# Ethernet.net
KiCad netlist of a schematic drawn in Altium Designer
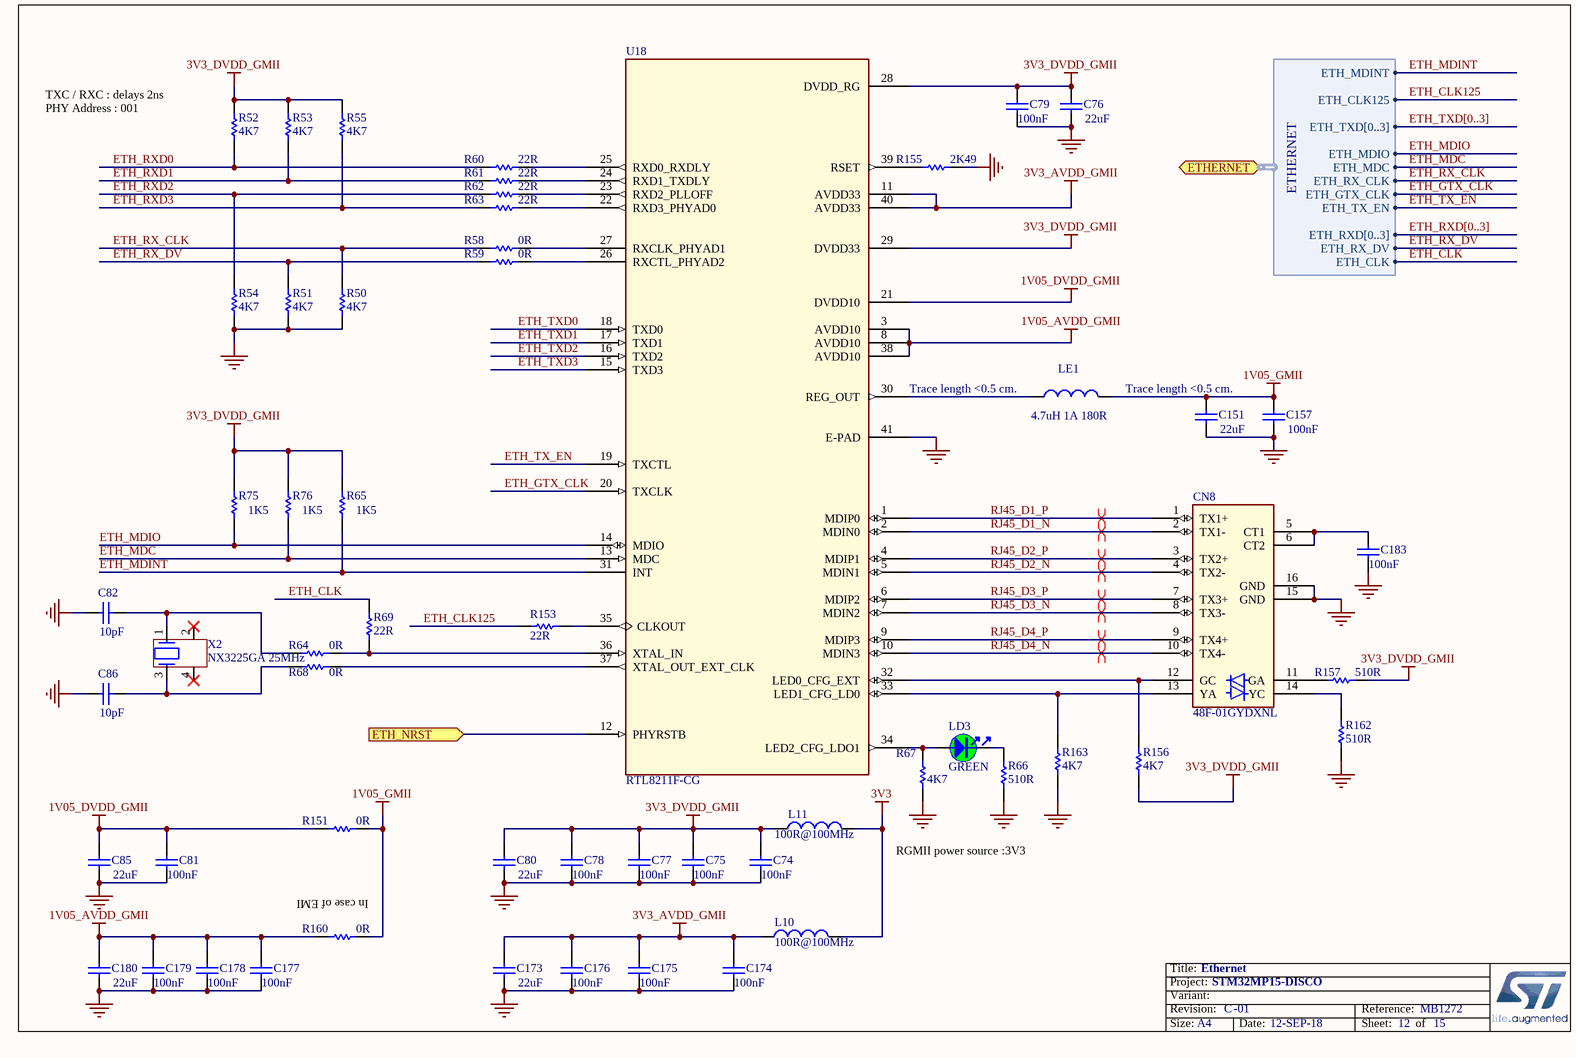
[diagram p0: Ethernet.SchDoc]

(export (version "E")
  (design (tool "Eeschema 10.0.6"))
  (components
    (comp (ref "C74")
      (value "100nF")
      (footprint "C0402")
      (description "Capacitor,100nF,16V,X7R,10%,0402")
      (fields
        (field (name "INTERNAL_PART_NUMBER") "MCD-00006")
        (field (name "MANUFACTURER_PART_NUMBER") "CC0402KRX7R7BB104")
        (field (name "PROVIDED_BY") "SUBCO")
      )
      (libsource (lib "MCD_PARTS_database") (part "Capacitor"))
    )
    (comp (ref "C75")
      (value "100nF")
      (footprint "C0402")
      (description "Capacitor,100nF,16V,X7R,10%,0402")
      (fields
        (field (name "INTERNAL_PART_NUMBER") "MCD-00006")
        (field (name "MANUFACTURER_PART_NUMBER") "CC0402KRX7R7BB104")
        (field (name "PROVIDED_BY") "SUBCO")
      )
      (libsource (lib "MCD_PARTS_database") (part "Capacitor"))
    )
    (comp (ref "C76")
      (value "22uF")
      (footprint "C0603")
      (description "Capacitor,22uF,6V3,X5R,20%,0603")
      (fields
        (field (name "INTERNAL_PART_NUMBER") "MCD-00100")
        (field (name "MANUFACTURER_PART_NUMBER") "GRM188R60J226MEA0J")
        (field (name "PROVIDED_BY") "SUBCO")
      )
      (libsource (lib "MCD_PARTS_database") (part "Capacitor"))
    )
    (comp (ref "C77")
      (value "100nF")
      (footprint "C0402")
      (description "Capacitor,100nF,16V,X7R,10%,0402")
      (fields
        (field (name "INTERNAL_PART_NUMBER") "MCD-00006")
        (field (name "MANUFACTURER_PART_NUMBER") "CC0402KRX7R7BB104")
        (field (name "PROVIDED_BY") "SUBCO")
      )
      (libsource (lib "MCD_PARTS_database") (part "Capacitor"))
    )
    (comp (ref "C78")
      (value "100nF")
      (footprint "C0402")
      (description "Capacitor,100nF,16V,X7R,10%,0402")
      (fields
        (field (name "INTERNAL_PART_NUMBER") "MCD-00006")
        (field (name "MANUFACTURER_PART_NUMBER") "CC0402KRX7R7BB104")
        (field (name "PROVIDED_BY") "SUBCO")
      )
      (libsource (lib "MCD_PARTS_database") (part "Capacitor"))
    )
    (comp (ref "C79")
      (value "100nF")
      (footprint "C0402")
      (description "Capacitor,100nF,16V,X7R,10%,0402")
      (fields
        (field (name "INTERNAL_PART_NUMBER") "MCD-00006")
        (field (name "MANUFACTURER_PART_NUMBER") "CC0402KRX7R7BB104")
        (field (name "PROVIDED_BY") "SUBCO")
      )
      (libsource (lib "MCD_PARTS_database") (part "Capacitor"))
    )
    (comp (ref "C80")
      (value "22uF")
      (footprint "C0603")
      (description "Capacitor,22uF,6V3,X5R,20%,0603")
      (fields
        (field (name "INTERNAL_PART_NUMBER") "MCD-00100")
        (field (name "MANUFACTURER_PART_NUMBER") "GRM188R60J226MEA0J")
        (field (name "PROVIDED_BY") "SUBCO")
      )
      (libsource (lib "MCD_PARTS_database") (part "Capacitor"))
    )
    (comp (ref "C81")
      (value "100nF")
      (footprint "C0402")
      (description "Capacitor,100nF,16V,X7R,10%,0402")
      (fields
        (field (name "INTERNAL_PART_NUMBER") "MCD-00006")
        (field (name "MANUFACTURER_PART_NUMBER") "CC0402KRX7R7BB104")
        (field (name "PROVIDED_BY") "SUBCO")
      )
      (libsource (lib "MCD_PARTS_database") (part "Capacitor"))
    )
    (comp (ref "C82")
      (value "10pF")
      (footprint "C0402")
      (description "Capacitor,10pF,50V,NPO,5%,0402")
      (fields
        (field (name "INTERNAL_PART_NUMBER") "MCD-00015")
        (field (name "MANUFACTURER_PART_NUMBER") "CC0402JRNPO9BN100")
        (field (name "PROVIDED_BY") "SUBCO")
      )
      (libsource (lib "MCD_PARTS_database") (part "Capacitor"))
    )
    (comp (ref "C85")
      (value "22uF")
      (footprint "C0603")
      (description "Capacitor,22uF,6V3,X5R,20%,0603")
      (fields
        (field (name "INTERNAL_PART_NUMBER") "MCD-00100")
        (field (name "MANUFACTURER_PART_NUMBER") "GRM188R60J226MEA0J")
        (field (name "PROVIDED_BY") "SUBCO")
      )
      (libsource (lib "MCD_PARTS_database") (part "Capacitor"))
    )
    (comp (ref "C86")
      (value "10pF")
      (footprint "C0402")
      (description "Capacitor,10pF,50V,NPO,5%,0402")
      (fields
        (field (name "INTERNAL_PART_NUMBER") "MCD-00015")
        (field (name "MANUFACTURER_PART_NUMBER") "CC0402JRNPO9BN100")
        (field (name "PROVIDED_BY") "SUBCO")
      )
      (libsource (lib "MCD_PARTS_database") (part "Capacitor"))
    )
    (comp (ref "C151")
      (value "22uF")
      (footprint "C0603")
      (description "Capacitor,22uF,6V3,X5R,20%,0603")
      (fields
        (field (name "INTERNAL_PART_NUMBER") "MCD-00100")
        (field (name "MANUFACTURER_PART_NUMBER") "GRM188R60J226MEA0J")
        (field (name "PROVIDED_BY") "SUBCO")
      )
      (libsource (lib "MCD_PARTS_database") (part "Capacitor"))
    )
    (comp (ref "C157")
      (value "100nF")
      (footprint "C0402")
      (description "Capacitor,100nF,16V,X7R,10%,0402")
      (fields
        (field (name "INTERNAL_PART_NUMBER") "MCD-00006")
        (field (name "MANUFACTURER_PART_NUMBER") "CC0402KRX7R7BB104")
        (field (name "PROVIDED_BY") "SUBCO")
      )
      (libsource (lib "MCD_PARTS_database") (part "Capacitor"))
    )
    (comp (ref "C173")
      (value "22uF")
      (footprint "C0603")
      (description "Capacitor,22uF,6V3,X5R,20%,0603")
      (fields
        (field (name "INTERNAL_PART_NUMBER") "MCD-00100")
        (field (name "MANUFACTURER_PART_NUMBER") "GRM188R60J226MEA0J")
        (field (name "PROVIDED_BY") "SUBCO")
      )
      (libsource (lib "MCD_PARTS_database") (part "Capacitor"))
    )
    (comp (ref "C174")
      (value "100nF")
      (footprint "C0402")
      (description "Capacitor,100nF,16V,X7R,10%,0402")
      (fields
        (field (name "INTERNAL_PART_NUMBER") "MCD-00006")
        (field (name "MANUFACTURER_PART_NUMBER") "CC0402KRX7R7BB104")
        (field (name "PROVIDED_BY") "SUBCO")
      )
      (libsource (lib "MCD_PARTS_database") (part "Capacitor"))
    )
    (comp (ref "C175")
      (value "100nF")
      (footprint "C0402")
      (description "Capacitor,100nF,16V,X7R,10%,0402")
      (fields
        (field (name "INTERNAL_PART_NUMBER") "MCD-00006")
        (field (name "MANUFACTURER_PART_NUMBER") "CC0402KRX7R7BB104")
        (field (name "PROVIDED_BY") "SUBCO")
      )
      (libsource (lib "MCD_PARTS_database") (part "Capacitor"))
    )
    (comp (ref "C176")
      (value "100nF")
      (footprint "C0402")
      (description "Capacitor,100nF,16V,X7R,10%,0402")
      (fields
        (field (name "INTERNAL_PART_NUMBER") "MCD-00006")
        (field (name "MANUFACTURER_PART_NUMBER") "CC0402KRX7R7BB104")
        (field (name "PROVIDED_BY") "SUBCO")
      )
      (libsource (lib "MCD_PARTS_database") (part "Capacitor"))
    )
    (comp (ref "C177")
      (value "100nF")
      (footprint "C0402")
      (description "Capacitor,100nF,16V,X7R,10%,0402")
      (fields
        (field (name "INTERNAL_PART_NUMBER") "MCD-00006")
        (field (name "MANUFACTURER_PART_NUMBER") "CC0402KRX7R7BB104")
        (field (name "PROVIDED_BY") "SUBCO")
      )
      (libsource (lib "MCD_PARTS_database") (part "Capacitor"))
    )
    (comp (ref "C178")
      (value "100nF")
      (footprint "C0402")
      (description "Capacitor,100nF,16V,X7R,10%,0402")
      (fields
        (field (name "INTERNAL_PART_NUMBER") "MCD-00006")
        (field (name "MANUFACTURER_PART_NUMBER") "CC0402KRX7R7BB104")
        (field (name "PROVIDED_BY") "SUBCO")
      )
      (libsource (lib "MCD_PARTS_database") (part "Capacitor"))
    )
    (comp (ref "C179")
      (value "100nF")
      (footprint "C0402")
      (description "Capacitor,100nF,16V,X7R,10%,0402")
      (fields
        (field (name "INTERNAL_PART_NUMBER") "MCD-00006")
        (field (name "MANUFACTURER_PART_NUMBER") "CC0402KRX7R7BB104")
        (field (name "PROVIDED_BY") "SUBCO")
      )
      (libsource (lib "MCD_PARTS_database") (part "Capacitor"))
    )
    (comp (ref "C180")
      (value "22uF")
      (footprint "C0603")
      (description "Capacitor,22uF,6V3,X5R,20%,0603")
      (fields
        (field (name "INTERNAL_PART_NUMBER") "MCD-00100")
        (field (name "MANUFACTURER_PART_NUMBER") "GRM188R60J226MEA0J")
        (field (name "PROVIDED_BY") "SUBCO")
      )
      (libsource (lib "MCD_PARTS_database") (part "Capacitor"))
    )
    (comp (ref "C183")
      (value "100nF")
      (footprint "C0402")
      (description "Capacitor,100nF,16V,X7R,10%,0402")
      (fields
        (field (name "INTERNAL_PART_NUMBER") "MCD-00006")
        (field (name "MANUFACTURER_PART_NUMBER") "CC0402KRX7R7BB104")
        (field (name "PROVIDED_BY") "SUBCO")
      )
      (libsource (lib "MCD_PARTS_database") (part "Capacitor"))
    )
    (comp (ref "CN8")
      (value "48F-01GYDXNL")
      (footprint "CON_RJ45_YD_48F-01GYDXNL_LED-P")
      (description "Connector RJ45 with Gigabit magnetics and LED , led pull down")
      (fields
        (field (name "INTERNAL_PART_NUMBER") "MCD-01129")
        (field (name "MANUFACTURER") "YUAN DEAN SCIENTIFIC")
        (field (name "PROVIDED_BY") "SUBCO")
      )
      (libsource (lib "MCD_PARTS_database") (part "RJ45_48F_01GYDXNL_LPD"))
    )
    (comp (ref "L10")
      (value "100R@100MHz")
      (footprint "FIL_0603_H0P65")
      (description "Ferrite bead 100R 2A 0603")
      (fields
        (field (name "INTERNAL_PART_NUMBER") "MCD-00094")
        (field (name "MANUFACTURER_PART_NUMBER") "BLM18EG101TN1")
        (field (name "PROVIDED_BY") "SUBCO")
      )
      (libsource (lib "MCD_PARTS_database") (part "BEAD"))
    )
    (comp (ref "L11")
      (value "100R@100MHz")
      (footprint "FIL_0603_H0P65")
      (description "Ferrite bead 100R 2A 0603")
      (fields
        (field (name "INTERNAL_PART_NUMBER") "MCD-00094")
        (field (name "MANUFACTURER_PART_NUMBER") "BLM18EG101TN1")
        (field (name "PROVIDED_BY") "SUBCO")
      )
      (libsource (lib "MCD_PARTS_database") (part "BEAD"))
    )
    (comp (ref "LD3")
      (value "GREEN")
      (footprint "LED_0603_GREEN")
      (description "LED, Green, 0603")
      (fields
        (field (name "INTERNAL_PART_NUMBER") "MCD-00050")
        (field (name "MANUFACTURER_PART_NUMBER") "19-213SYGC/S530-E2/TR8")
        (field (name "PROVIDED_BY") "SUBCO")
      )
      (libsource (lib "MCD_PARTS_database") (part "LED_green"))
    )
    (comp (ref "LE1")
      (value "4.7uH 1A 180R")
      (footprint "L1210_LQH")
      (description "FIXED IND 4.7UH 1A 180 MOHM 30% SMD")
      (fields
        (field (name "INTERNAL_PART_NUMBER") "MCD-00048")
        (field (name "MANUFACTURER_PART_NUMBER") "LQH32PN4R7NN0L")
        (field (name "PROVIDED_BY") "SUBCO")
      )
      (libsource (lib "MCD_PARTS_database") (part "Inductor"))
    )
    (comp (ref "R50")
      (value "4K7")
      (footprint "R0402")
      (description "Resistor,4K7,0402,1%,1/16W")
      (fields
        (field (name "INTERNAL_PART_NUMBER") "MCD-00065")
        (field (name "MANUFACTURER_PART_NUMBER") "RC0402FR-074K7L")
        (field (name "PROVIDED_BY") "SUBCO")
      )
      (libsource (lib "MCD_PARTS_database") (part "Resistor"))
    )
    (comp (ref "R51")
      (value "4K7")
      (footprint "R0402")
      (description "Resistor,4K7,0402,1%,1/16W")
      (fields
        (field (name "INTERNAL_PART_NUMBER") "MCD-00065")
        (field (name "MANUFACTURER_PART_NUMBER") "RC0402FR-074K7L")
        (field (name "PROVIDED_BY") "SUBCO")
      )
      (libsource (lib "MCD_PARTS_database") (part "Resistor"))
    )
    (comp (ref "R52")
      (value "4K7")
      (footprint "R0402")
      (description "Resistor,4K7,0402,1%,1/16W")
      (fields
        (field (name "INTERNAL_PART_NUMBER") "MCD-00065")
        (field (name "MANUFACTURER_PART_NUMBER") "RC0402FR-074K7L")
        (field (name "PROVIDED_BY") "SUBCO")
      )
      (libsource (lib "MCD_PARTS_database") (part "Resistor"))
    )
    (comp (ref "R53")
      (value "4K7")
      (footprint "R0402")
      (description "Resistor,4K7,0402,1%,1/16W")
      (fields
        (field (name "INTERNAL_PART_NUMBER") "MCD-00065")
        (field (name "MANUFACTURER_PART_NUMBER") "RC0402FR-074K7L")
        (field (name "PROVIDED_BY") "SUBCO")
      )
      (libsource (lib "MCD_PARTS_database") (part "Resistor"))
    )
    (comp (ref "R54")
      (value "4K7")
      (footprint "R0402")
      (description "Resistor,4K7,0402,1%,1/16W")
      (fields
        (field (name "INTERNAL_PART_NUMBER") "MCD-00065")
        (field (name "MANUFACTURER_PART_NUMBER") "RC0402FR-074K7L")
        (field (name "PROVIDED_BY") "SUBCO")
      )
      (libsource (lib "MCD_PARTS_database") (part "Resistor"))
    )
    (comp (ref "R55")
      (value "4K7")
      (footprint "R0402")
      (description "Resistor,4K7,0402,1%,1/16W")
      (fields
        (field (name "INTERNAL_PART_NUMBER") "MCD-00065")
        (field (name "MANUFACTURER_PART_NUMBER") "RC0402FR-074K7L")
        (field (name "PROVIDED_BY") "SUBCO")
      )
      (libsource (lib "MCD_PARTS_database") (part "Resistor"))
    )
    (comp (ref "R58")
      (value "0R")
      (footprint "R0402")
      (description "Resistor,0R,0402,5%,1/16W")
      (fields
        (field (name "INTERNAL_PART_NUMBER") "MCD-00052")
        (field (name "MANUFACTURER_PART_NUMBER") "RC0402JR-070RL")
        (field (name "PROVIDED_BY") "SUBCO")
      )
      (libsource (lib "MCD_PARTS_database") (part "Resistor"))
    )
    (comp (ref "R59")
      (value "0R")
      (footprint "R0402")
      (description "Resistor,0R,0402,5%,1/16W")
      (fields
        (field (name "INTERNAL_PART_NUMBER") "MCD-00052")
        (field (name "MANUFACTURER_PART_NUMBER") "RC0402JR-070RL")
        (field (name "PROVIDED_BY") "SUBCO")
      )
      (libsource (lib "MCD_PARTS_database") (part "Resistor"))
    )
    (comp (ref "R60")
      (value "22R")
      (footprint "R0402")
      (description "Resistor,22R,0402,1%,1/16W")
      (fields
        (field (name "INTERNAL_PART_NUMBER") "MCD-00189")
        (field (name "MANUFACTURER_PART_NUMBER") "RC0402FR-0722RL")
        (field (name "PROVIDED_BY") "SUBCO")
      )
      (libsource (lib "MCD_PARTS_database") (part "Resistor"))
    )
    (comp (ref "R61")
      (value "22R")
      (footprint "R0402")
      (description "Resistor,22R,0402,1%,1/16W")
      (fields
        (field (name "INTERNAL_PART_NUMBER") "MCD-00189")
        (field (name "MANUFACTURER_PART_NUMBER") "RC0402FR-0722RL")
        (field (name "PROVIDED_BY") "SUBCO")
      )
      (libsource (lib "MCD_PARTS_database") (part "Resistor"))
    )
    (comp (ref "R62")
      (value "22R")
      (footprint "R0402")
      (description "Resistor,22R,0402,1%,1/16W")
      (fields
        (field (name "INTERNAL_PART_NUMBER") "MCD-00189")
        (field (name "MANUFACTURER_PART_NUMBER") "RC0402FR-0722RL")
        (field (name "PROVIDED_BY") "SUBCO")
      )
      (libsource (lib "MCD_PARTS_database") (part "Resistor"))
    )
    (comp (ref "R63")
      (value "22R")
      (footprint "R0402")
      (description "Resistor,22R,0402,1%,1/16W")
      (fields
        (field (name "INTERNAL_PART_NUMBER") "MCD-00189")
        (field (name "MANUFACTURER_PART_NUMBER") "RC0402FR-0722RL")
        (field (name "PROVIDED_BY") "SUBCO")
      )
      (libsource (lib "MCD_PARTS_database") (part "Resistor"))
    )
    (comp (ref "R64")
      (value "0R")
      (footprint "R0402")
      (description "Resistor,0R,0402,5%,1/16W")
      (fields
        (field (name "INTERNAL_PART_NUMBER") "MCD-00052")
        (field (name "MANUFACTURER_PART_NUMBER") "RC0402JR-070RL")
        (field (name "PROVIDED_BY") "SUBCO")
      )
      (libsource (lib "MCD_PARTS_database") (part "Resistor"))
    )
    (comp (ref "R65")
      (value "1K5")
      (footprint "R0402")
      (description "Resistor,1K5,0402,1%,1/16W")
      (fields
        (field (name "INTERNAL_PART_NUMBER") "MCD-00068")
        (field (name "MANUFACTURER_PART_NUMBER") "RC0402FR-071K5L")
        (field (name "PROVIDED_BY") "SUBCO")
      )
      (libsource (lib "MCD_PARTS_database") (part "Resistor"))
    )
    (comp (ref "R66")
      (value "510R")
      (footprint "R0402")
      (description "Resistor,510R,0402,1%,1/16W")
      (fields
        (field (name "INTERNAL_PART_NUMBER") "MCD-00064")
        (field (name "MANUFACTURER_PART_NUMBER") "RC0402FR-07510RL")
        (field (name "PROVIDED_BY") "SUBCO")
      )
      (libsource (lib "MCD_PARTS_database") (part "Resistor"))
    )
    (comp (ref "R67")
      (value "4K7")
      (footprint "R0402")
      (description "Resistor,4K7,0402,1%,1/16W")
      (fields
        (field (name "INTERNAL_PART_NUMBER") "MCD-00065")
        (field (name "MANUFACTURER_PART_NUMBER") "RC0402FR-074K7L")
        (field (name "PROVIDED_BY") "SUBCO")
      )
      (libsource (lib "MCD_PARTS_database") (part "Resistor"))
    )
    (comp (ref "R68")
      (value "0R")
      (footprint "R0402")
      (description "Resistor,0R,0402,5%,1/16W")
      (fields
        (field (name "INTERNAL_PART_NUMBER") "MCD-00052")
        (field (name "MANUFACTURER_PART_NUMBER") "RC0402JR-070RL")
        (field (name "PROVIDED_BY") "SUBCO")
      )
      (libsource (lib "MCD_PARTS_database") (part "Resistor"))
    )
    (comp (ref "R69")
      (value "22R")
      (footprint "R0402")
      (description "Resistor,22R,0402,1%,1/16W")
      (fields
        (field (name "INTERNAL_PART_NUMBER") "MCD-00189")
        (field (name "MANUFACTURER_PART_NUMBER") "RC0402FR-0722RL")
        (field (name "PROVIDED_BY") "SUBCO")
      )
      (libsource (lib "MCD_PARTS_database") (part "Resistor"))
    )
    (comp (ref "R75")
      (value "1K5")
      (footprint "R0402")
      (description "Resistor,1K5,0402,1%,1/16W")
      (fields
        (field (name "INTERNAL_PART_NUMBER") "MCD-00068")
        (field (name "MANUFACTURER_PART_NUMBER") "RC0402FR-071K5L")
        (field (name "PROVIDED_BY") "SUBCO")
      )
      (libsource (lib "MCD_PARTS_database") (part "Resistor"))
    )
    (comp (ref "R76")
      (value "1K5")
      (footprint "R0402")
      (description "Resistor,1K5,0402,1%,1/16W")
      (fields
        (field (name "INTERNAL_PART_NUMBER") "MCD-00068")
        (field (name "MANUFACTURER_PART_NUMBER") "RC0402FR-071K5L")
        (field (name "PROVIDED_BY") "SUBCO")
      )
      (libsource (lib "MCD_PARTS_database") (part "Resistor"))
    )
    (comp (ref "R151")
      (value "0R")
      (footprint "R0603")
      (description "Resistor,0R,0603,5%,1/10W")
      (fields
        (field (name "INTERNAL_PART_NUMBER") "MCD-00056")
        (field (name "MANUFACTURER_PART_NUMBER") "RC0603JR-070RL")
        (field (name "PROVIDED_BY") "SUBCO")
      )
      (libsource (lib "MCD_PARTS_database") (part "Resistor"))
    )
    (comp (ref "R153")
      (value "22R")
      (footprint "R0402")
      (description "Resistor,22R,0402,1%,1/16W")
      (fields
        (field (name "INTERNAL_PART_NUMBER") "MCD-00189")
        (field (name "MANUFACTURER_PART_NUMBER") "RC0402FR-0722RL")
        (field (name "PROVIDED_BY") "SUBCO")
      )
      (libsource (lib "MCD_PARTS_database") (part "Resistor"))
    )
    (comp (ref "R155")
      (value "2K49")
      (footprint "R0402")
      (description "Resistor,2K49,0402,1%,1/16W")
      (fields
        (field (name "INTERNAL_PART_NUMBER") "MCD-00183")
        (field (name "MANUFACTURER_PART_NUMBER") "RC0402FR-072K49L")
        (field (name "PROVIDED_BY") "SUBCO")
      )
      (libsource (lib "MCD_PARTS_database") (part "Resistor"))
    )
    (comp (ref "R156")
      (value "4K7")
      (footprint "R0402")
      (description "Resistor,4K7,0402,1%,1/16W")
      (fields
        (field (name "INTERNAL_PART_NUMBER") "MCD-00065")
        (field (name "MANUFACTURER_PART_NUMBER") "RC0402FR-074K7L")
        (field (name "PROVIDED_BY") "SUBCO")
      )
      (libsource (lib "MCD_PARTS_database") (part "Resistor"))
    )
    (comp (ref "R157")
      (value "510R")
      (footprint "R0402")
      (description "Resistor,510R,0402,1%,1/16W")
      (fields
        (field (name "INTERNAL_PART_NUMBER") "MCD-00064")
        (field (name "MANUFACTURER_PART_NUMBER") "RC0402FR-07510RL")
        (field (name "PROVIDED_BY") "SUBCO")
      )
      (libsource (lib "MCD_PARTS_database") (part "Resistor"))
    )
    (comp (ref "R160")
      (value "0R")
      (footprint "R0603")
      (description "Resistor,0R,0603,5%,1/10W")
      (fields
        (field (name "INTERNAL_PART_NUMBER") "MCD-00056")
        (field (name "MANUFACTURER_PART_NUMBER") "RC0603JR-070RL")
        (field (name "PROVIDED_BY") "SUBCO")
      )
      (libsource (lib "MCD_PARTS_database") (part "Resistor"))
    )
    (comp (ref "R162")
      (value "510R")
      (footprint "R0402")
      (description "Resistor,510R,0402,1%,1/16W")
      (fields
        (field (name "INTERNAL_PART_NUMBER") "MCD-00064")
        (field (name "MANUFACTURER_PART_NUMBER") "RC0402FR-07510RL")
        (field (name "PROVIDED_BY") "SUBCO")
      )
      (libsource (lib "MCD_PARTS_database") (part "Resistor"))
    )
    (comp (ref "R163")
      (value "4K7")
      (footprint "R0402")
      (description "Resistor,4K7,0402,1%,1/16W")
      (fields
        (field (name "INTERNAL_PART_NUMBER") "MCD-00065")
        (field (name "MANUFACTURER_PART_NUMBER") "RC0402FR-074K7L")
        (field (name "PROVIDED_BY") "SUBCO")
      )
      (libsource (lib "MCD_PARTS_database") (part "Resistor"))
    )
    (comp (ref "U18")
      (value "RTL8211F-CG")
      (footprint "ICC_QFN40-EPAD_5X5_P040")
      (description "10/100/1000M GIGABIT Ethernet Transceiver, QFN40 , SMPS version")
      (fields
        (field (name "INTERNAL_PART_NUMBER") "MCD-01130")
        (field (name "MANUFACTURER") "REALTEK")
        (field (name "PROVIDED_BY") "SUBCO")
      )
      (libsource (lib "MCD_PARTS_database") (part "RTL8211F-CG"))
    )
    (comp (ref "X2")
      (value "NX3225GA 25MHz")
      (footprint "CRY_NX3225HA_4P")
      (description "Crystal 25Mhz, 10pF, -+50PPM, SMD")
      (fields
        (field (name "INTERNAL_PART_NUMBER") "MCD-01463")
        (field (name "MANUFACTURER_PART_NUMBER") "NX3225GA 25MHz EXS00A-CG06750")
        (field (name "PROVIDED_BY") "SUBCO")
      )
      (libsource (lib "MCD_PARTS_database") (part "XTAL_4_PINS"))
    )
  )
  (nets
    (net (code "2") (name "/ETH_CLK") (class "Default")
      (node (ref "R69") (pin "2") (pinfunction "2_2") (pintype "passive"))
    )
    (net (code "3") (name "/ETH_CLK125") (class "Default")
      (node (ref "R153") (pin "1") (pinfunction "1_1") (pintype "passive"))
    )
    (net (code "4") (name "/ETH_GTX_CLK") (class "Default")
      (node (ref "U18") (pin "20") (pinfunction "TXCLK_20") (pintype "input"))
    )
    (net (code "5") (name "/ETH_MDC") (class "Default")
      (node (ref "R76") (pin "1") (pinfunction "1_1") (pintype "passive"))
      (node (ref "U18") (pin "13") (pinfunction "MDC_13") (pintype "input"))
    )
    (net (code "6") (name "/ETH_MDINT") (class "Default")
      (node (ref "R65") (pin "1") (pinfunction "1_1") (pintype "passive"))
      (node (ref "U18") (pin "31") (pinfunction "INT_31") (pintype "passive"))
    )
    (net (code "7") (name "/ETH_MDIO") (class "Default")
      (node (ref "R75") (pin "1") (pinfunction "1_1") (pintype "passive"))
      (node (ref "U18") (pin "14") (pinfunction "MDIO_14") (pintype "bidirectional"))
    )
    (net (code "8") (name "/ETH_NRST") (class "Default")
      (node (ref "U18") (pin "12") (pinfunction "PHYRSTB_12") (pintype "input"))
    )
    (net (code "9") (name "/ETH_RXD0") (class "Default")
      (node (ref "R52") (pin "1") (pinfunction "1_1") (pintype "passive"))
      (node (ref "R60") (pin "1") (pinfunction "1_1") (pintype "passive"))
    )
    (net (code "10") (name "/ETH_RXD1") (class "Default")
      (node (ref "R53") (pin "1") (pinfunction "1_1") (pintype "passive"))
      (node (ref "R61") (pin "1") (pinfunction "1_1") (pintype "passive"))
    )
    (net (code "11") (name "/ETH_RXD2") (class "Default")
      (node (ref "R54") (pin "2") (pinfunction "2_2") (pintype "passive"))
      (node (ref "R62") (pin "1") (pinfunction "1_1") (pintype "passive"))
    )
    (net (code "12") (name "/ETH_RXD3") (class "Default")
      (node (ref "R55") (pin "1") (pinfunction "1_1") (pintype "passive"))
      (node (ref "R63") (pin "1") (pinfunction "1_1") (pintype "passive"))
    )
    (net (code "14") (name "/ETH_RX_CLK") (class "Default")
      (node (ref "R50") (pin "2") (pinfunction "2_2") (pintype "passive"))
      (node (ref "R58") (pin "1") (pinfunction "1_1") (pintype "passive"))
    )
    (net (code "15") (name "/ETH_RX_DV") (class "Default")
      (node (ref "R51") (pin "2") (pinfunction "2_2") (pintype "passive"))
      (node (ref "R59") (pin "1") (pinfunction "1_1") (pintype "passive"))
    )
    (net (code "16") (name "/ETH_TXD0") (class "Default")
      (node (ref "U18") (pin "18") (pinfunction "TXD0_18") (pintype "input"))
    )
    (net (code "17") (name "/ETH_TXD1") (class "Default")
      (node (ref "U18") (pin "17") (pinfunction "TXD1_17") (pintype "input"))
    )
    (net (code "18") (name "/ETH_TXD2") (class "Default")
      (node (ref "U18") (pin "16") (pinfunction "TXD2_16") (pintype "input"))
    )
    (net (code "19") (name "/ETH_TXD3") (class "Default")
      (node (ref "U18") (pin "15") (pinfunction "TXD3_15") (pintype "input"))
    )
    (net (code "21") (name "/ETH_TX_EN") (class "Default")
      (node (ref "U18") (pin "19") (pinfunction "TXCTL_19") (pintype "input"))
    )
    (net (code "22") (name "/RJ45_D1_N") (class "Default")
      (node (ref "CN8") (pin "2") (pinfunction "TX1-_2") (pintype "bidirectional"))
      (node (ref "U18") (pin "2") (pinfunction "MDIN0_2") (pintype "bidirectional"))
    )
    (net (code "23") (name "/RJ45_D1_P") (class "Default")
      (node (ref "CN8") (pin "1") (pinfunction "TX1+_1") (pintype "bidirectional"))
      (node (ref "U18") (pin "1") (pinfunction "MDIP0_1") (pintype "bidirectional"))
    )
    (net (code "24") (name "/RJ45_D2_N") (class "Default")
      (node (ref "CN8") (pin "4") (pinfunction "TX2-_4") (pintype "bidirectional"))
      (node (ref "U18") (pin "5") (pinfunction "MDIN1_5") (pintype "bidirectional"))
    )
    (net (code "25") (name "/RJ45_D2_P") (class "Default")
      (node (ref "CN8") (pin "3") (pinfunction "TX2+_3") (pintype "bidirectional"))
      (node (ref "U18") (pin "4") (pinfunction "MDIP1_4") (pintype "bidirectional"))
    )
    (net (code "26") (name "/RJ45_D3_N") (class "Default")
      (node (ref "CN8") (pin "8") (pinfunction "TX3-_8") (pintype "bidirectional"))
      (node (ref "U18") (pin "7") (pinfunction "MDIN2_7") (pintype "bidirectional"))
    )
    (net (code "27") (name "/RJ45_D3_P") (class "Default")
      (node (ref "CN8") (pin "7") (pinfunction "TX3+_7") (pintype "bidirectional"))
      (node (ref "U18") (pin "6") (pinfunction "MDIP2_6") (pintype "bidirectional"))
    )
    (net (code "28") (name "/RJ45_D4_N") (class "Default")
      (node (ref "CN8") (pin "10") (pinfunction "TX4-_10") (pintype "bidirectional"))
      (node (ref "U18") (pin "10") (pinfunction "MDIN3_10") (pintype "bidirectional"))
    )
    (net (code "29") (name "/RJ45_D4_P") (class "Default")
      (node (ref "CN8") (pin "9") (pinfunction "TX4+_9") (pintype "bidirectional"))
      (node (ref "U18") (pin "9") (pinfunction "MDIP3_9") (pintype "bidirectional"))
    )
    (net (code "31") (name "1V05_AVDD_GMII") (class "Default")
      (node (ref "C177") (pin "2") (pinfunction "2_2") (pintype "passive"))
      (node (ref "C178") (pin "2") (pinfunction "2_2") (pintype "passive"))
      (node (ref "C179") (pin "2") (pinfunction "2_2") (pintype "passive"))
      (node (ref "C180") (pin "2") (pinfunction "2_2") (pintype "passive"))
      (node (ref "R160") (pin "1") (pinfunction "1_1") (pintype "passive"))
      (node (ref "U18") (pin "3") (pinfunction "AVDD10_3") (pintype "power_in"))
      (node (ref "U18") (pin "38") (pinfunction "AVDD10_38") (pintype "power_in"))
      (node (ref "U18") (pin "8") (pinfunction "AVDD10_8") (pintype "power_in"))
    )
    (net (code "32") (name "1V05_DVDD_GMII") (class "Default")
      (node (ref "C81") (pin "2") (pinfunction "2_2") (pintype "passive"))
      (node (ref "C85") (pin "2") (pinfunction "2_2") (pintype "passive"))
      (node (ref "R151") (pin "1") (pinfunction "1_1") (pintype "passive"))
      (node (ref "U18") (pin "21") (pinfunction "DVDD10_21") (pintype "power_in"))
    )
    (net (code "33") (name "1V05_GMII") (class "Default")
      (node (ref "C151") (pin "2") (pinfunction "2_2") (pintype "passive"))
      (node (ref "C157") (pin "2") (pinfunction "2_2") (pintype "passive"))
      (node (ref "LE1") (pin "2") (pinfunction "2_2") (pintype "passive"))
      (node (ref "R151") (pin "2") (pinfunction "2_2") (pintype "passive"))
      (node (ref "R160") (pin "2") (pinfunction "2_2") (pintype "passive"))
    )
    (net (code "34") (name "3V3") (class "Default")
      (node (ref "L10") (pin "2") (pinfunction "2_2") (pintype "passive"))
      (node (ref "L11") (pin "2") (pinfunction "2_2") (pintype "passive"))
    )
    (net (code "35") (name "3V3_AVDD_GMII") (class "Default")
      (node (ref "C173") (pin "2") (pinfunction "2_2") (pintype "passive"))
      (node (ref "C174") (pin "2") (pinfunction "2_2") (pintype "passive"))
      (node (ref "C175") (pin "2") (pinfunction "2_2") (pintype "passive"))
      (node (ref "C176") (pin "2") (pinfunction "2_2") (pintype "passive"))
      (node (ref "L10") (pin "1") (pinfunction "1_1") (pintype "passive"))
      (node (ref "U18") (pin "11") (pinfunction "AVDD33_11") (pintype "power_in"))
      (node (ref "U18") (pin "40") (pinfunction "AVDD33_40") (pintype "power_in"))
    )
    (net (code "36") (name "3V3_DVDD_GMII") (class "Default")
      (node (ref "C74") (pin "2") (pinfunction "2_2") (pintype "passive"))
      (node (ref "C75") (pin "2") (pinfunction "2_2") (pintype "passive"))
      (node (ref "C76") (pin "1") (pinfunction "1_1") (pintype "passive"))
      (node (ref "C77") (pin "2") (pinfunction "2_2") (pintype "passive"))
      (node (ref "C78") (pin "2") (pinfunction "2_2") (pintype "passive"))
      (node (ref "C79") (pin "2") (pinfunction "2_2") (pintype "passive"))
      (node (ref "C80") (pin "2") (pinfunction "2_2") (pintype "passive"))
      (node (ref "L11") (pin "1") (pinfunction "1_1") (pintype "passive"))
      (node (ref "R156") (pin "1") (pinfunction "1_1") (pintype "passive"))
      (node (ref "R157") (pin "2") (pinfunction "2_2") (pintype "passive"))
      (node (ref "R52") (pin "2") (pinfunction "2_2") (pintype "passive"))
      (node (ref "R53") (pin "2") (pinfunction "2_2") (pintype "passive"))
      (node (ref "R55") (pin "2") (pinfunction "2_2") (pintype "passive"))
      (node (ref "R65") (pin "2") (pinfunction "2_2") (pintype "passive"))
      (node (ref "R75") (pin "2") (pinfunction "2_2") (pintype "passive"))
      (node (ref "R76") (pin "2") (pinfunction "2_2") (pintype "passive"))
      (node (ref "U18") (pin "28") (pinfunction "DVDD_RG_28") (pintype "power_in"))
      (node (ref "U18") (pin "29") (pinfunction "DVDD33_29") (pintype "power_in"))
    )
    (net (code "37") (name "GND") (class "Default")
      (node (ref "C151") (pin "1") (pinfunction "1_1") (pintype "passive"))
      (node (ref "C157") (pin "1") (pinfunction "1_1") (pintype "passive"))
      (node (ref "C173") (pin "1") (pinfunction "1_1") (pintype "passive"))
      (node (ref "C174") (pin "1") (pinfunction "1_1") (pintype "passive"))
      (node (ref "C175") (pin "1") (pinfunction "1_1") (pintype "passive"))
      (node (ref "C176") (pin "1") (pinfunction "1_1") (pintype "passive"))
      (node (ref "C177") (pin "1") (pinfunction "1_1") (pintype "passive"))
      (node (ref "C178") (pin "1") (pinfunction "1_1") (pintype "passive"))
      (node (ref "C179") (pin "1") (pinfunction "1_1") (pintype "passive"))
      (node (ref "C180") (pin "1") (pinfunction "1_1") (pintype "passive"))
      (node (ref "C183") (pin "1") (pinfunction "1_1") (pintype "passive"))
      (node (ref "C74") (pin "1") (pinfunction "1_1") (pintype "passive"))
      (node (ref "C75") (pin "1") (pinfunction "1_1") (pintype "passive"))
      (node (ref "C76") (pin "2") (pinfunction "2_2") (pintype "passive"))
      (node (ref "C77") (pin "1") (pinfunction "1_1") (pintype "passive"))
      (node (ref "C78") (pin "1") (pinfunction "1_1") (pintype "passive"))
      (node (ref "C79") (pin "1") (pinfunction "1_1") (pintype "passive"))
      (node (ref "C80") (pin "1") (pinfunction "1_1") (pintype "passive"))
      (node (ref "C81") (pin "1") (pinfunction "1_1") (pintype "passive"))
      (node (ref "C82") (pin "1") (pinfunction "1_1") (pintype "passive"))
      (node (ref "C85") (pin "1") (pinfunction "1_1") (pintype "passive"))
      (node (ref "C86") (pin "1") (pinfunction "1_1") (pintype "passive"))
      (node (ref "CN8") (pin "15") (pinfunction "GND_15") (pintype "power_in"))
      (node (ref "CN8") (pin "16") (pinfunction "GND_16") (pintype "power_in"))
      (node (ref "R155") (pin "2") (pinfunction "2_2") (pintype "passive"))
      (node (ref "R162") (pin "1") (pinfunction "1_1") (pintype "passive"))
      (node (ref "R163") (pin "1") (pinfunction "1_1") (pintype "passive"))
      (node (ref "R50") (pin "1") (pinfunction "1_1") (pintype "passive"))
      (node (ref "R51") (pin "1") (pinfunction "1_1") (pintype "passive"))
      (node (ref "R54") (pin "1") (pinfunction "1_1") (pintype "passive"))
      (node (ref "R66") (pin "1") (pinfunction "1_1") (pintype "passive"))
      (node (ref "R67") (pin "1") (pinfunction "1_1") (pintype "passive"))
      (node (ref "U18") (pin "41") (pinfunction "E-PAD_41") (pintype "power_in"))
    )
    (net (code "38") (name "Net-(C82-Pad2)") (class "Default")
      (node (ref "C82") (pin "2") (pinfunction "2_2") (pintype "passive"))
      (node (ref "R64") (pin "1") (pinfunction "1_1") (pintype "passive"))
      (node (ref "X2") (pin "1") (pinfunction "1_1") (pintype "passive"))
    )
    (net (code "39") (name "Net-(C86-Pad2)") (class "Default")
      (node (ref "C86") (pin "2") (pinfunction "2_2") (pintype "passive"))
      (node (ref "R68") (pin "1") (pinfunction "1_1") (pintype "passive"))
      (node (ref "X2") (pin "3") (pinfunction "3_3") (pintype "passive"))
    )
    (net (code "40") (name "Net-(CN8-CT1)") (class "Default")
      (node (ref "C183") (pin "2") (pinfunction "2_2") (pintype "passive"))
      (node (ref "CN8") (pin "5") (pinfunction "CT1_5") (pintype "passive"))
      (node (ref "CN8") (pin "6") (pinfunction "CT2_6") (pintype "passive"))
    )
    (net (code "41") (name "Net-(CN8-GA)") (class "Default")
      (node (ref "CN8") (pin "11") (pinfunction "GA_11") (pintype "passive"))
      (node (ref "R157") (pin "1") (pinfunction "1_1") (pintype "passive"))
    )
    (net (code "42") (name "Net-(CN8-GC)") (class "Default")
      (node (ref "CN8") (pin "12") (pinfunction "GC_12") (pintype "passive"))
      (node (ref "R156") (pin "2") (pinfunction "2_2") (pintype "passive"))
      (node (ref "U18") (pin "32") (pinfunction "LED0_CFG_EXT_32") (pintype "bidirectional"))
    )
    (net (code "43") (name "Net-(CN8-YA)") (class "Default")
      (node (ref "CN8") (pin "13") (pinfunction "YA_13") (pintype "passive"))
      (node (ref "R163") (pin "2") (pinfunction "2_2") (pintype "passive"))
      (node (ref "U18") (pin "33") (pinfunction "LED1_CFG_LD0_33") (pintype "bidirectional"))
    )
    (net (code "44") (name "Net-(CN8-YC)") (class "Default")
      (node (ref "CN8") (pin "14") (pinfunction "YC_14") (pintype "passive"))
      (node (ref "R162") (pin "2") (pinfunction "2_2") (pintype "passive"))
    )
    (net (code "45") (name "Net-(LD3-Pad2)") (class "Default")
      (node (ref "LD3") (pin "2") (pintype "passive"))
      (node (ref "R66") (pin "2") (pinfunction "2_2") (pintype "passive"))
    )
    (net (code "46") (name "Net-(U18-CLKOUT)") (class "Default")
      (node (ref "R153") (pin "2") (pinfunction "2_2") (pintype "passive"))
      (node (ref "U18") (pin "35") (pinfunction "CLKOUT_35") (pintype "output"))
    )
    (net (code "47") (name "Net-(U18-LED2_CFG_LDO1)") (class "Default")
      (node (ref "LD3") (pin "1") (pintype "passive"))
      (node (ref "R67") (pin "2") (pinfunction "2_2") (pintype "passive"))
      (node (ref "U18") (pin "34") (pinfunction "LED2_CFG_LDO1_34") (pintype "output"))
    )
    (net (code "48") (name "Net-(U18-REG_OUT)") (class "Default")
      (node (ref "LE1") (pin "1") (pinfunction "1_1") (pintype "passive"))
      (node (ref "U18") (pin "30") (pinfunction "REG_OUT_30") (pintype "output"))
    )
    (net (code "49") (name "Net-(U18-RSET)") (class "Default")
      (node (ref "R155") (pin "1") (pinfunction "1_1") (pintype "passive"))
      (node (ref "U18") (pin "39") (pinfunction "RSET_39") (pintype "output"))
    )
    (net (code "50") (name "Net-(U18-RXCLK_PHYAD1)") (class "Default")
      (node (ref "R58") (pin "2") (pinfunction "2_2") (pintype "passive"))
      (node (ref "U18") (pin "27") (pinfunction "RXCLK_PHYAD1_27") (pintype "passive"))
    )
    (net (code "51") (name "Net-(U18-RXCTL_PHYAD2)") (class "Default")
      (node (ref "R59") (pin "2") (pinfunction "2_2") (pintype "passive"))
      (node (ref "U18") (pin "26") (pinfunction "RXCTL_PHYAD2_26") (pintype "passive"))
    )
    (net (code "52") (name "Net-(U18-RXD0_RXDLY)") (class "Default")
      (node (ref "R60") (pin "2") (pinfunction "2_2") (pintype "passive"))
      (node (ref "U18") (pin "25") (pinfunction "RXD0_RXDLY_25") (pintype "output"))
    )
    (net (code "53") (name "Net-(U18-RXD1_TXDLY)") (class "Default")
      (node (ref "R61") (pin "2") (pinfunction "2_2") (pintype "passive"))
      (node (ref "U18") (pin "24") (pinfunction "RXD1_TXDLY_24") (pintype "output"))
    )
    (net (code "54") (name "Net-(U18-RXD2_PLLOFF)") (class "Default")
      (node (ref "R62") (pin "2") (pinfunction "2_2") (pintype "passive"))
      (node (ref "U18") (pin "23") (pinfunction "RXD2_PLLOFF_23") (pintype "output"))
    )
    (net (code "55") (name "Net-(U18-RXD3_PHYAD0)") (class "Default")
      (node (ref "R63") (pin "2") (pinfunction "2_2") (pintype "passive"))
      (node (ref "U18") (pin "22") (pinfunction "RXD3_PHYAD0_22") (pintype "output"))
    )
    (net (code "56") (name "Net-(U18-XTAL_IN)") (class "Default")
      (node (ref "R64") (pin "2") (pinfunction "2_2") (pintype "passive"))
      (node (ref "R69") (pin "1") (pinfunction "1_1") (pintype "passive"))
      (node (ref "U18") (pin "36") (pinfunction "XTAL_IN_36") (pintype "input"))
    )
    (net (code "57") (name "Net-(U18-XTAL_OUT_EXT_CLK)") (class "Default")
      (node (ref "R68") (pin "2") (pinfunction "2_2") (pintype "passive"))
      (node (ref "U18") (pin "37") (pinfunction "XTAL_OUT_EXT_CLK_37") (pintype "output"))
    )
    (net (code "58") (name "unconnected-(X2-Pad2)") (class "Default")
      (node (ref "X2") (pin "2") (pinfunction "2_2") (pintype "passive+no_connect"))
    )
    (net (code "59") (name "unconnected-(X2-Pad4)") (class "Default")
      (node (ref "X2") (pin "4") (pinfunction "4_4") (pintype "passive+no_connect"))
    )
  )
)
